# Sheet2.net
KiCad netlist of a schematic drawn in Altium Designer
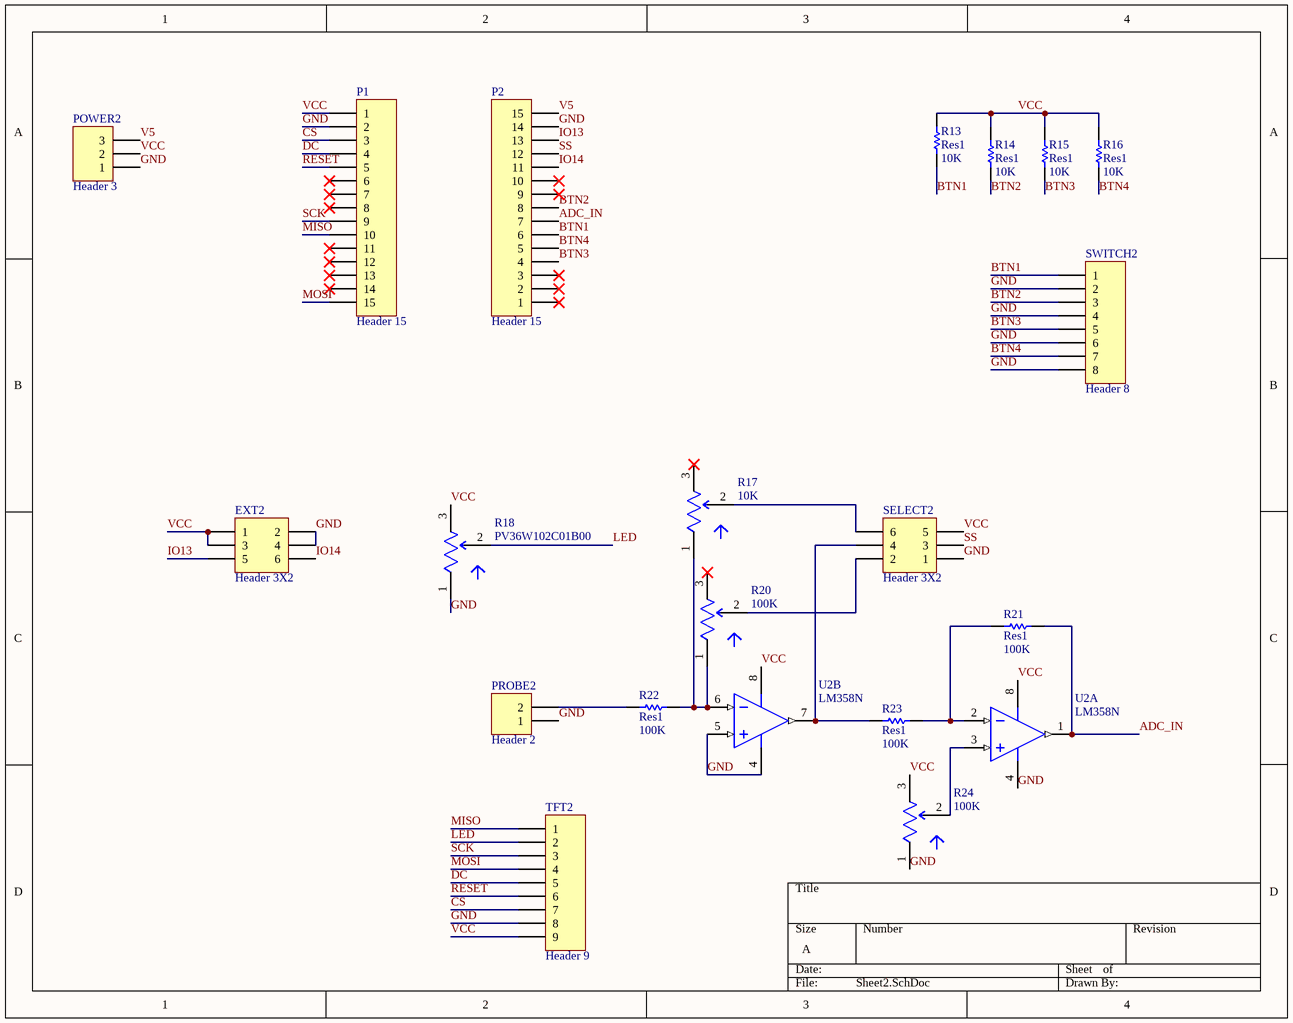
[diagram p0: Sheet2.SchDoc]

(export (version "E")
  (design (tool "Eeschema 10.0.6"))
  (components
    (comp (ref "EXT2")
      (value "Header 3X2")
      (footprint "HDR2X3")
      (description "Header, 3-Pin, Dual row")
      (fields (field (name "PUBLISHER") "Altium Limited"))
      (libsource (lib "") (part "Header 3X2_1"))
    )
    (comp (ref "P1")
      (value "Header 15")
      (footprint "HDR1X15")
      (description "Header, 15-Pin")
      (fields (field (name "PUBLISHER") "Altium Limited"))
      (libsource (lib "") (part "Header 15_1"))
    )
    (comp (ref "P2")
      (value "Header 15")
      (footprint "HDR1X15")
      (description "Header, 15-Pin")
      (fields (field (name "PUBLISHER") "Altium Limited"))
      (libsource (lib "Miscellaneous Connectors") (part "Header 15"))
    )
    (comp (ref "POWER2")
      (value "Header 3")
      (footprint "HDR1X3")
      (description "Header, 3-Pin")
      (fields (field (name "PUBLISHER") "Altium Limited"))
      (libsource (lib "Miscellaneous Connectors") (part "Header 3"))
    )
    (comp (ref "PROBE2")
      (value "Header 2")
      (footprint "HDR1X2")
      (description "Header, 2-Pin")
      (fields (field (name "PUBLISHER") "Altium Limited"))
      (libsource (lib "Miscellaneous Connectors") (part "Header 2"))
    )
    (comp (ref "R13")
      (value "Res1")
      (footprint "AXIAL-0.3")
      (description "Resistor")
      (fields (field (name "ALTIUM_VALUE") "10K") (field (name "PUBLISHER") "Altium Limited"))
      (libsource (lib "Miscellaneous Devices") (part "Res1"))
    )
    (comp (ref "R14")
      (value "Res1")
      (footprint "AXIAL-0.3")
      (description "Resistor")
      (fields (field (name "ALTIUM_VALUE") "10K") (field (name "PUBLISHER") "Altium Limited"))
      (libsource (lib "Miscellaneous Devices") (part "Res1"))
    )
    (comp (ref "R15")
      (value "Res1")
      (footprint "AXIAL-0.3")
      (description "Resistor")
      (fields (field (name "ALTIUM_VALUE") "10K") (field (name "PUBLISHER") "Altium Limited"))
      (libsource (lib "Miscellaneous Devices") (part "Res1"))
    )
    (comp (ref "R16")
      (value "Res1")
      (footprint "AXIAL-0.3")
      (description "Resistor")
      (fields (field (name "ALTIUM_VALUE") "10K") (field (name "PUBLISHER") "Altium Limited"))
      (libsource (lib "Miscellaneous Devices") (part "Res1"))
    )
    (comp (ref "R17")
      (value "10K")
      (footprint "FP-PV36W-MFG")
      (description "TRIMMER 1K OHM 0.5W PC PIN TOP")
      (fields
        (field (name "OCTOPART") "https://octopart.com/pv36w102c01b00-bourns-71612321")
        (field (name "MANUFACTURER PART NUMBER") "PV36W102C01B00")
      )
      (libsource (lib "Altium Content Vault") (part "3b5a993e1b8b55ba5d1e0805a406c64"))
    )
    (comp (ref "R18")
      (value "PV36W102C01B00")
      (footprint "FP-PV36W-MFG")
      (description "TRIMMER 1K OHM 0.5W PC PIN TOP")
      (fields
        (field (name "OCTOPART") "https://octopart.com/pv36w102c01b00-bourns-71612321")
        (field (name "TOLERANCE") "10%")
      )
      (libsource (lib "Altium Content Vault") (part "3b5a993e1b8b55ba5d1e0805a406c64"))
    )
    (comp (ref "R20")
      (value "100K")
      (footprint "FP-PV36W-MFG")
      (description "TRIMMER 1K OHM 0.5W PC PIN TOP")
      (fields
        (field (name "OCTOPART") "https://octopart.com/pv36w102c01b00-bourns-71612321")
        (field (name "MANUFACTURER PART NUMBER") "PV36W102C01B00")
      )
      (libsource (lib "Altium Content Vault") (part "3b5a993e1b8b55ba5d1e0805a406c64"))
    )
    (comp (ref "R21")
      (value "Res1")
      (footprint "AXIAL-0.3")
      (description "Resistor")
      (fields (field (name "ALTIUM_VALUE") "100K") (field (name "PUBLISHER") "Altium Limited"))
      (libsource (lib "Miscellaneous Devices") (part "Res1"))
    )
    (comp (ref "R22")
      (value "Res1")
      (footprint "AXIAL-0.3")
      (description "Resistor")
      (fields (field (name "ALTIUM_VALUE") "100K") (field (name "PUBLISHER") "Altium Limited"))
      (libsource (lib "Miscellaneous Devices") (part "Res1"))
    )
    (comp (ref "R23")
      (value "Res1")
      (footprint "AXIAL-0.3")
      (description "Resistor")
      (fields (field (name "ALTIUM_VALUE") "100K") (field (name "PUBLISHER") "Altium Limited"))
      (libsource (lib "Miscellaneous Devices") (part "Res1"))
    )
    (comp (ref "R24")
      (value "100K")
      (footprint "FP-PV36W-MFG")
      (description "TRIMMER 1K OHM 0.5W PC PIN TOP")
      (fields
        (field (name "OCTOPART") "https://octopart.com/pv36w102c01b00-bourns-71612321")
        (field (name "MANUFACTURER PART NUMBER") "PV36W102C01B00")
      )
      (libsource (lib "Altium Content Vault") (part "3b5a993e1b8b55ba5d1e0805a406c64"))
    )
    (comp (ref "SELECT2")
      (value "Header 3X2")
      (footprint "HDR2X3")
      (description "Header, 3-Pin, Dual row")
      (fields (field (name "PUBLISHER") "Altium Limited"))
      (libsource (lib "Miscellaneous Connectors") (part "Header 3X2"))
    )
    (comp (ref "SWITCH2")
      (value "Header 8")
      (footprint "HDR1X8")
      (description "Header, 8-Pin")
      (fields (field (name "PUBLISHER") "Altium Limited"))
      (libsource (lib "Miscellaneous Connectors") (part "Header 8"))
    )
    (comp (ref "TFT2")
      (value "Header 9")
      (footprint "HDR1X9")
      (description "Header, 9-Pin")
      (fields (field (name "PUBLISHER") "Altium Limited"))
      (libsource (lib "Miscellaneous Connectors") (part "Header 9"))
    )
    (comp (ref "U2")
      (value "LM358N")
      (footprint "ONSC-PDIP-8-626-05_M")
      (description "Single Supply Dual Operational Amplifier, 3 to 32 V, 0 to 70 degC, 8-Pin PDIP, Tube")
      (fields (field (name "MANUFACTURER") "On Semiconductor"))
      (libsource (lib "Altium Content Vault") (part "ONSC-LM358_NCV2904-8"))
    )
  )
  (nets
    (net (code "1") (name "/ADC_IN") (class "Default")
      (node (ref "P2") (pin "7") (pinfunction "7_7") (pintype "passive"))
      (node (ref "R21") (pin "1") (pinfunction "1_1") (pintype "passive"))
      (node (ref "U2") (pin "1") (pinfunction "OUTA_1") (pintype "output"))
    )
    (net (code "2") (name "/BTN1") (class "Default")
      (node (ref "P2") (pin "6") (pinfunction "6_6") (pintype "passive"))
      (node (ref "R13") (pin "1") (pinfunction "1_1") (pintype "passive"))
      (node (ref "SWITCH2") (pin "1") (pinfunction "1_1") (pintype "passive"))
    )
    (net (code "3") (name "/BTN2") (class "Default")
      (node (ref "P2") (pin "8") (pinfunction "8_8") (pintype "passive"))
      (node (ref "R14") (pin "1") (pinfunction "1_1") (pintype "passive"))
      (node (ref "SWITCH2") (pin "3") (pinfunction "3_3") (pintype "passive"))
    )
    (net (code "4") (name "/BTN3") (class "Default")
      (node (ref "P2") (pin "4") (pinfunction "4_4") (pintype "passive"))
      (node (ref "R15") (pin "1") (pinfunction "1_1") (pintype "passive"))
      (node (ref "SWITCH2") (pin "5") (pinfunction "5_5") (pintype "passive"))
    )
    (net (code "5") (name "/BTN4") (class "Default")
      (node (ref "P2") (pin "5") (pinfunction "5_5") (pintype "passive"))
      (node (ref "R16") (pin "1") (pinfunction "1_1") (pintype "passive"))
      (node (ref "SWITCH2") (pin "7") (pinfunction "7_7") (pintype "passive"))
    )
    (net (code "6") (name "/CS") (class "Default")
      (node (ref "P1") (pin "3") (pinfunction "3_3") (pintype "passive"))
      (node (ref "TFT2") (pin "7") (pinfunction "7_7") (pintype "passive"))
    )
    (net (code "7") (name "/DC") (class "Default")
      (node (ref "P1") (pin "4") (pinfunction "4_4") (pintype "passive"))
      (node (ref "TFT2") (pin "5") (pinfunction "5_5") (pintype "passive"))
    )
    (net (code "8") (name "/GND") (class "Default")
      (node (ref "EXT2") (pin "2") (pinfunction "2_2") (pintype "passive"))
      (node (ref "EXT2") (pin "4") (pinfunction "4_4") (pintype "passive"))
      (node (ref "P1") (pin "2") (pinfunction "2_2") (pintype "passive"))
      (node (ref "P2") (pin "14") (pinfunction "14_14") (pintype "passive"))
      (node (ref "POWER2") (pin "1") (pinfunction "1_1") (pintype "passive"))
      (node (ref "PROBE2") (pin "1") (pinfunction "1_1") (pintype "passive"))
      (node (ref "R18") (pin "1") (pinfunction "1_1") (pintype "passive"))
      (node (ref "R24") (pin "1") (pinfunction "1_1") (pintype "passive"))
      (node (ref "SELECT2") (pin "1") (pinfunction "1_1") (pintype "passive"))
      (node (ref "SWITCH2") (pin "2") (pinfunction "2_2") (pintype "passive"))
      (node (ref "SWITCH2") (pin "4") (pinfunction "4_4") (pintype "passive"))
      (node (ref "SWITCH2") (pin "6") (pinfunction "6_6") (pintype "passive"))
      (node (ref "SWITCH2") (pin "8") (pinfunction "8_8") (pintype "passive"))
      (node (ref "TFT2") (pin "8") (pinfunction "8_8") (pintype "passive"))
      (node (ref "U2") (pin "4") (pinfunction "VEE/GND_4") (pintype "power_in"))
      (node (ref "U2") (pin "5") (pinfunction "INB+_5") (pintype "input"))
    )
    (net (code "9") (name "/IO13") (class "Default")
      (node (ref "EXT2") (pin "5") (pinfunction "5_5") (pintype "passive"))
      (node (ref "P2") (pin "13") (pinfunction "13_13") (pintype "passive"))
    )
    (net (code "10") (name "/IO14") (class "Default")
      (node (ref "EXT2") (pin "6") (pinfunction "6_6") (pintype "passive"))
      (node (ref "P2") (pin "11") (pinfunction "11_11") (pintype "passive"))
    )
    (net (code "11") (name "/LED") (class "Default")
      (node (ref "R18") (pin "2") (pinfunction "Wiper_2") (pintype "passive"))
      (node (ref "TFT2") (pin "2") (pinfunction "2_2") (pintype "passive"))
    )
    (net (code "12") (name "/MISO") (class "Default")
      (node (ref "P1") (pin "10") (pinfunction "10_10") (pintype "passive"))
      (node (ref "TFT2") (pin "1") (pinfunction "1_1") (pintype "passive"))
    )
    (net (code "13") (name "/MOSI") (class "Default")
      (node (ref "P1") (pin "15") (pinfunction "15_15") (pintype "passive"))
      (node (ref "TFT2") (pin "4") (pinfunction "4_4") (pintype "passive"))
    )
    (net (code "14") (name "/RESET") (class "Default")
      (node (ref "P1") (pin "5") (pinfunction "5_5") (pintype "passive"))
      (node (ref "TFT2") (pin "6") (pinfunction "6_6") (pintype "passive"))
    )
    (net (code "15") (name "/SCK") (class "Default")
      (node (ref "P1") (pin "9") (pinfunction "9_9") (pintype "passive"))
      (node (ref "TFT2") (pin "3") (pinfunction "3_3") (pintype "passive"))
    )
    (net (code "16") (name "/SS") (class "Default")
      (node (ref "P2") (pin "12") (pinfunction "12_12") (pintype "passive"))
      (node (ref "SELECT2") (pin "3") (pinfunction "3_3") (pintype "passive"))
    )
    (net (code "17") (name "/V5") (class "Default")
      (node (ref "P2") (pin "15") (pinfunction "15_15") (pintype "passive"))
      (node (ref "POWER2") (pin "3") (pinfunction "3_3") (pintype "passive"))
    )
    (net (code "18") (name "/VCC") (class "Default")
      (node (ref "EXT2") (pin "1") (pinfunction "1_1") (pintype "passive"))
      (node (ref "EXT2") (pin "3") (pinfunction "3_3") (pintype "passive"))
      (node (ref "P1") (pin "1") (pinfunction "1_1") (pintype "passive"))
      (node (ref "POWER2") (pin "2") (pinfunction "2_2") (pintype "passive"))
      (node (ref "R13") (pin "2") (pinfunction "2_2") (pintype "passive"))
      (node (ref "R14") (pin "2") (pinfunction "2_2") (pintype "passive"))
      (node (ref "R15") (pin "2") (pinfunction "2_2") (pintype "passive"))
      (node (ref "R16") (pin "2") (pinfunction "2_2") (pintype "passive"))
      (node (ref "R18") (pin "3") (pinfunction "3_3") (pintype "passive"))
      (node (ref "R24") (pin "3") (pinfunction "3_3") (pintype "passive"))
      (node (ref "SELECT2") (pin "5") (pinfunction "5_5") (pintype "passive"))
      (node (ref "TFT2") (pin "9") (pinfunction "9_9") (pintype "passive"))
      (node (ref "U2") (pin "8") (pinfunction "VCC_8") (pintype "power_in"))
    )
    (net (code "19") (name "Net-(PROBE2-Pad2)") (class "Default")
      (node (ref "PROBE2") (pin "2") (pinfunction "2_2") (pintype "passive"))
      (node (ref "R22") (pin "2") (pinfunction "2_2") (pintype "passive"))
    )
    (net (code "20") (name "Net-(R17-Wiper)") (class "Default")
      (node (ref "R17") (pin "2") (pinfunction "Wiper_2") (pintype "passive"))
      (node (ref "SELECT2") (pin "6") (pinfunction "6_6") (pintype "passive"))
    )
    (net (code "21") (name "Net-(R20-Wiper)") (class "Default")
      (node (ref "R20") (pin "2") (pinfunction "Wiper_2") (pintype "passive"))
      (node (ref "SELECT2") (pin "2") (pinfunction "2_2") (pintype "passive"))
    )
    (net (code "22") (name "Net-(R24-Wiper)") (class "Default")
      (node (ref "R24") (pin "2") (pinfunction "Wiper_2") (pintype "passive"))
      (node (ref "U2") (pin "3") (pinfunction "INA+_3") (pintype "input"))
    )
    (net (code "23") (name "Net-(U2A-INA-)") (class "Default")
      (node (ref "R21") (pin "2") (pinfunction "2_2") (pintype "passive"))
      (node (ref "R23") (pin "1") (pinfunction "1_1") (pintype "passive"))
      (node (ref "U2") (pin "2") (pinfunction "INA-_2") (pintype "input"))
    )
    (net (code "24") (name "Net-(U2B-INB-)") (class "Default")
      (node (ref "R17") (pin "1") (pinfunction "1_1") (pintype "passive"))
      (node (ref "R20") (pin "1") (pinfunction "1_1") (pintype "passive"))
      (node (ref "R22") (pin "1") (pinfunction "1_1") (pintype "passive"))
      (node (ref "U2") (pin "6") (pinfunction "INB-_6") (pintype "input"))
    )
    (net (code "25") (name "Net-(U2B-OUTB)") (class "Default")
      (node (ref "R23") (pin "2") (pinfunction "2_2") (pintype "passive"))
      (node (ref "SELECT2") (pin "4") (pinfunction "4_4") (pintype "passive"))
      (node (ref "U2") (pin "7") (pinfunction "OUTB_7") (pintype "output"))
    )
    (net (code "26") (name "unconnected-(P1-Pad6)") (class "Default")
      (node (ref "P1") (pin "6") (pinfunction "6_6") (pintype "passive+no_connect"))
    )
    (net (code "27") (name "unconnected-(P1-Pad7)") (class "Default")
      (node (ref "P1") (pin "7") (pinfunction "7_7") (pintype "passive+no_connect"))
    )
    (net (code "28") (name "unconnected-(P1-Pad8)") (class "Default")
      (node (ref "P1") (pin "8") (pinfunction "8_8") (pintype "passive+no_connect"))
    )
    (net (code "29") (name "unconnected-(P1-Pad11)") (class "Default")
      (node (ref "P1") (pin "11") (pinfunction "11_11") (pintype "passive+no_connect"))
    )
    (net (code "30") (name "unconnected-(P1-Pad12)") (class "Default")
      (node (ref "P1") (pin "12") (pinfunction "12_12") (pintype "passive+no_connect"))
    )
    (net (code "31") (name "unconnected-(P1-Pad13)") (class "Default")
      (node (ref "P1") (pin "13") (pinfunction "13_13") (pintype "passive+no_connect"))
    )
    (net (code "32") (name "unconnected-(P1-Pad14)") (class "Default")
      (node (ref "P1") (pin "14") (pinfunction "14_14") (pintype "passive+no_connect"))
    )
    (net (code "33") (name "unconnected-(P2-Pad1)") (class "Default")
      (node (ref "P2") (pin "1") (pinfunction "1_1") (pintype "passive+no_connect"))
    )
    (net (code "34") (name "unconnected-(P2-Pad2)") (class "Default")
      (node (ref "P2") (pin "2") (pinfunction "2_2") (pintype "passive+no_connect"))
    )
    (net (code "35") (name "unconnected-(P2-Pad3)") (class "Default")
      (node (ref "P2") (pin "3") (pinfunction "3_3") (pintype "passive+no_connect"))
    )
    (net (code "36") (name "unconnected-(P2-Pad9)") (class "Default")
      (node (ref "P2") (pin "9") (pinfunction "9_9") (pintype "passive+no_connect"))
    )
    (net (code "37") (name "unconnected-(P2-Pad10)") (class "Default")
      (node (ref "P2") (pin "10") (pinfunction "10_10") (pintype "passive+no_connect"))
    )
    (net (code "38") (name "unconnected-(R17-Pad3)") (class "Default")
      (node (ref "R17") (pin "3") (pinfunction "3_3") (pintype "passive+no_connect"))
    )
    (net (code "39") (name "unconnected-(R20-Pad3)") (class "Default")
      (node (ref "R20") (pin "3") (pinfunction "3_3") (pintype "passive+no_connect"))
    )
  )
)
